# Sheet8.net
KiCad netlist of a schematic drawn in Altium Designer
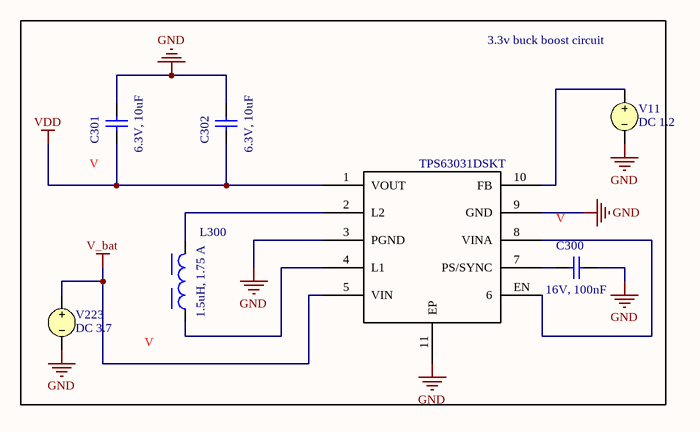
[diagram p0: Sheet8.SchDoc]

(export (version "E")
  (design (tool "Eeschema 10.0.6"))
  (components
    (comp (ref "C300")
      (value "16V, 100nF")
      (footprint "WCAP-CSGP_0603_L1.6W0.8H0.8_Reflow")
      (description "Cap Ceramic 0.1uF 16V X7R 10% Pad SMD 0603 125C T/R")
      (fields (field (name "TOLERANCE") "10%"))
      (libsource (lib "Altium Content Vault") (part "Capacitor_Non-Polarized"))
    )
    (comp (ref "C301")
      (value "6.3V, 10uF")
      (footprint "WCAP-CSGP_0603_L1.6W0.8H0.8_Reflow")
      (fields (field (name "TOLERANCE") "20%"))
      (libsource (lib "Altium Content Vault") (part "Capacitor_Non-Polarized"))
    )
    (comp (ref "C302")
      (value "6.3V, 10uF")
      (footprint "WCAP-CSGP_0603_L1.6W0.8H0.8_Reflow")
      (fields (field (name "TOLERANCE") "20%"))
      (libsource (lib "Altium Content Vault") (part "Capacitor_Non-Polarized"))
    )
    (comp (ref "L300")
      (value "1.5uH, 1.75 A")
      (footprint "WE-TPC_3816")
      (description "100KHz 125MHz 1.55A 1.75A 1.5μH 47mΩ ±30% standard mounting，SMD mount 3.8mm*3.8mm*1.8mm")
      (fields (field (name "TOLERANCE") "30%"))
      (libsource (lib "Altium Content Vault") (part "Inductor - 3"))
    )
    (comp (ref "U300")
      (value "TPS63031DSKT")
      (footprint "TPS63031DSKT")
      (description "High Efficient Single Inductor Buck-Boost Converter with 1-A Switches 10-SON -40 to 125")
      (libsource (lib "Schlib1") (part "TPS63031DSKT"))
    )
    (comp (ref "V11")
      (value "DC 1.2")
      (description "Voltage Source")
      (fields (field (name "PUBLISHER") "Altium Limited"))
      (libsource (lib "Simulation Generic Components") (part "VSRC"))
    )
    (comp (ref "V223")
      (value "DC 3.7")
      (description "Voltage Source")
      (fields (field (name "PUBLISHER") "Altium Limited"))
      (libsource (lib "Simulation Generic Components") (part "VSRC"))
    )
  )
  (nets
    (net (code "1") (name "GND") (class "Default")
      (node (ref "C300") (pin "2") (pinfunction "2_2") (pintype "passive"))
      (node (ref "C301") (pin "2") (pinfunction "2_2") (pintype "passive"))
      (node (ref "C302") (pin "2") (pinfunction "2_2") (pintype "passive"))
      (node (ref "U300") (pin "11") (pinfunction "EP_11") (pintype "passive"))
      (node (ref "U300") (pin "3") (pinfunction "PGND_3") (pintype "passive"))
      (node (ref "U300") (pin "9") (pinfunction "GND_9") (pintype "passive"))
      (node (ref "V11") (pin "2") (pinfunction "2_2") (pintype "passive"))
      (node (ref "V223") (pin "2") (pinfunction "2_2") (pintype "passive"))
    )
    (net (code "2") (name "Net-(U300-6)") (class "Default")
      (node (ref "U300") (pin "8") (pinfunction "VINA_8") (pintype "passive"))
      (node (ref "U300") (pin "EN") (pinfunction "6_EN") (pintype "passive"))
    )
    (net (code "3") (name "Net-(U300-FB)") (class "Default")
      (node (ref "U300") (pin "10") (pinfunction "FB_10") (pintype "passive"))
      (node (ref "V11") (pin "1") (pinfunction "1_1") (pintype "passive"))
    )
    (net (code "4") (name "Net-(U300-L1)") (class "Default")
      (node (ref "L300") (pin "1") (pinfunction "1_1") (pintype "passive"))
      (node (ref "U300") (pin "4") (pinfunction "L1_4") (pintype "passive"))
    )
    (net (code "5") (name "Net-(U300-L2)") (class "Default")
      (node (ref "L300") (pin "2") (pinfunction "2_2") (pintype "passive"))
      (node (ref "U300") (pin "2") (pinfunction "L2_2") (pintype "passive"))
    )
    (net (code "6") (name "Net-(U300-PS{slash}SYNC)") (class "Default")
      (node (ref "C300") (pin "1") (pinfunction "1_1") (pintype "passive"))
      (node (ref "U300") (pin "7") (pinfunction "PS/SYNC_7") (pintype "passive"))
    )
    (net (code "7") (name "VDD") (class "Default")
      (node (ref "C301") (pin "1") (pinfunction "1_1") (pintype "passive"))
      (node (ref "C302") (pin "1") (pinfunction "1_1") (pintype "passive"))
      (node (ref "U300") (pin "1") (pinfunction "VOUT_1") (pintype "passive"))
    )
    (net (code "8") (name "V_bat") (class "Default")
      (node (ref "U300") (pin "5") (pinfunction "VIN_5") (pintype "passive"))
      (node (ref "V223") (pin "1") (pinfunction "1_1") (pintype "passive"))
    )
  )
)
